# mcp23017-board.net
KiCad netlist of a schematic drawn in EAGLE
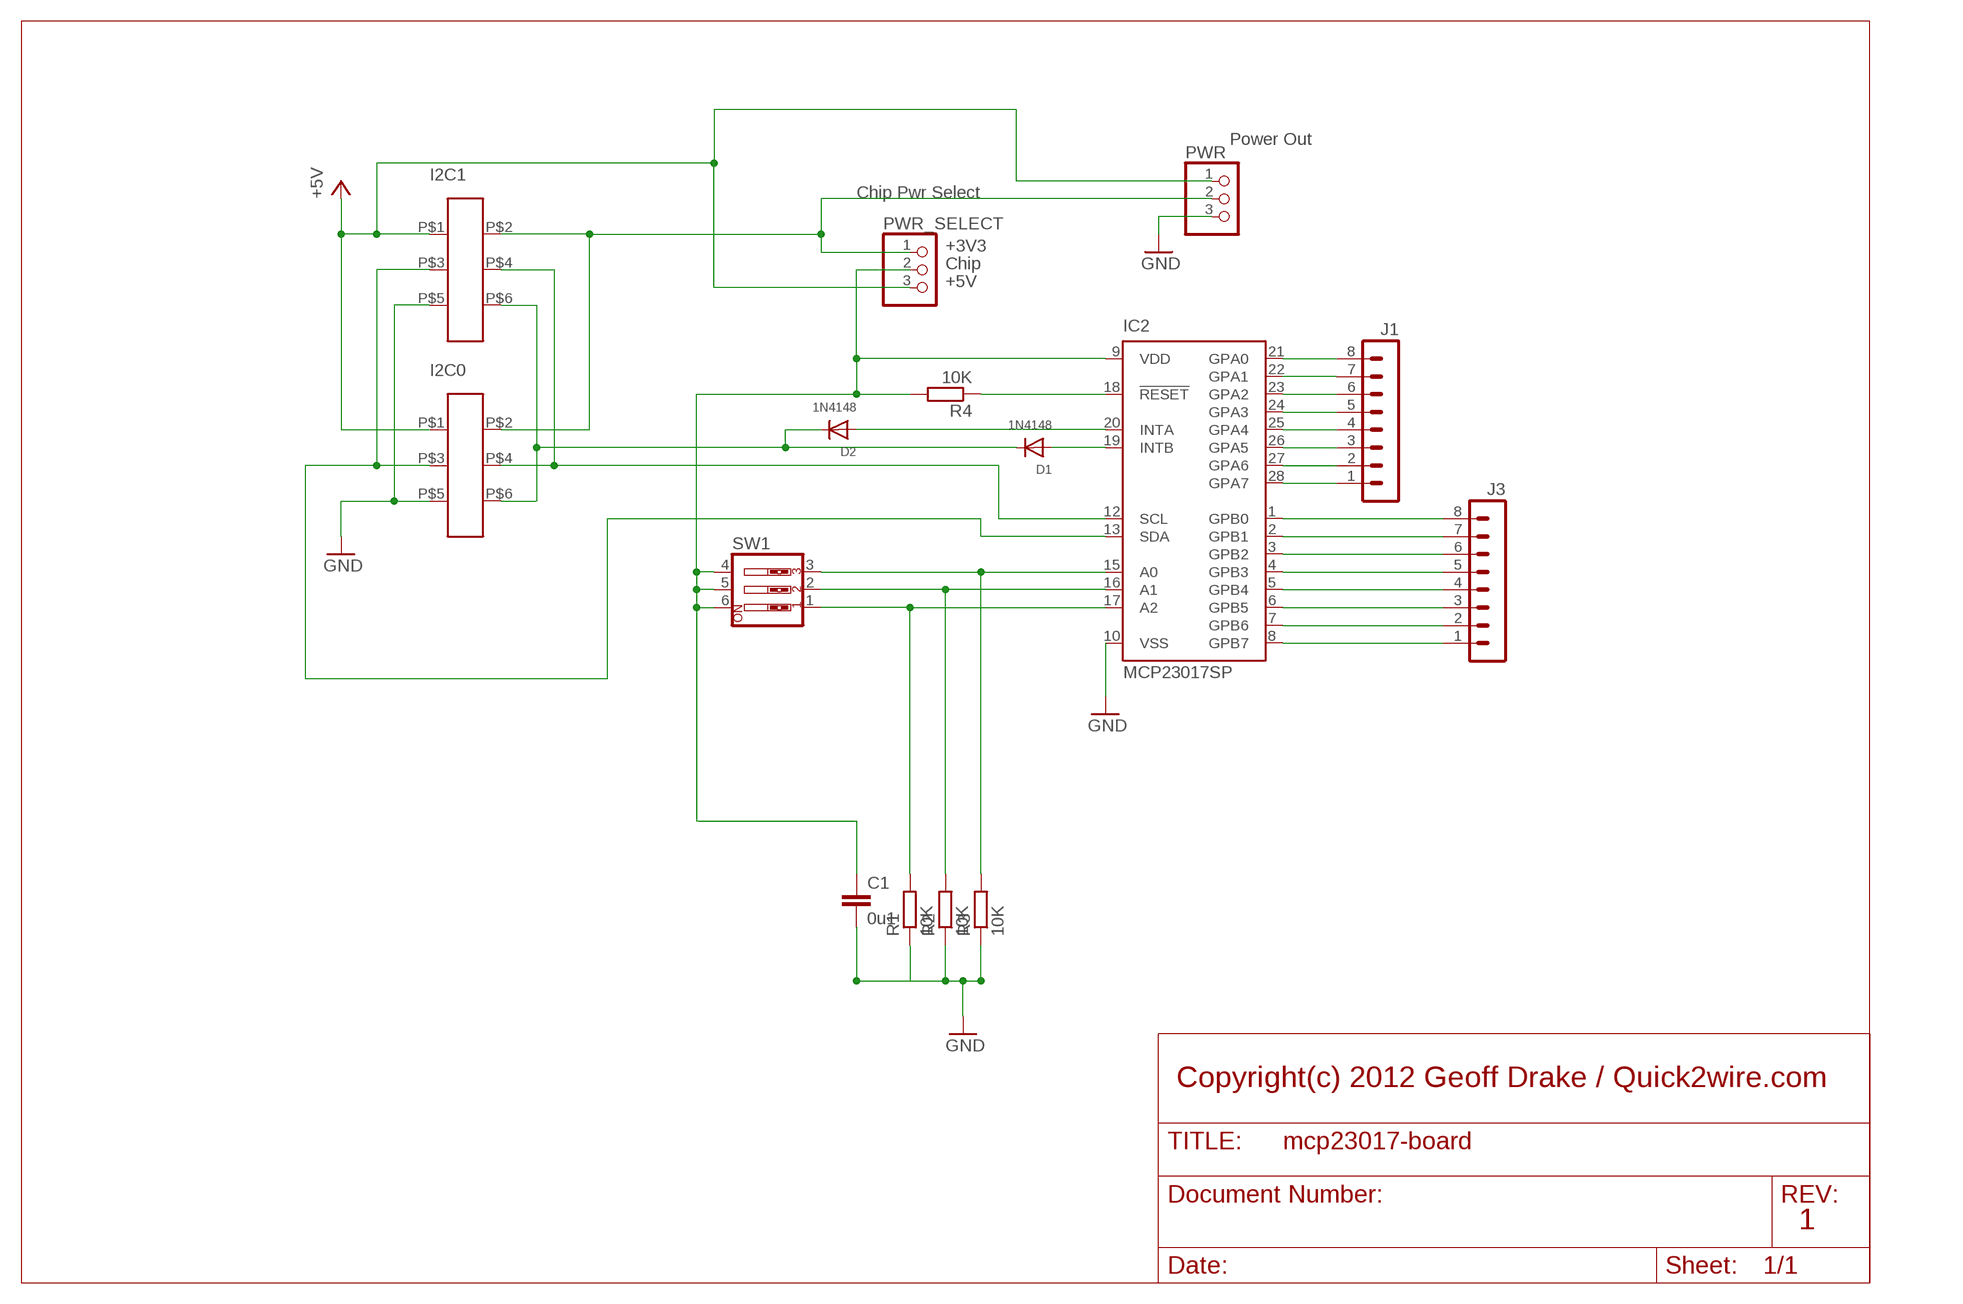
[diagram p0: schematic, sheet 1]

(export (version "E")
  (design (tool "Eeschema 10.0.6"))
  (components
    (comp (ref "C1")
      (value "0u1")
      (footprint "eagle-import:C025-030X050")
      (libsource (lib "eagle-import") (part "C-EU025-030X050"))
    )
    (comp (ref "D1")
      (value "1N4148")
      (footprint "eagle-import:DO-1N4148")
      (libsource (lib "eagle-import") (part "DIODEDO-1N4148"))
    )
    (comp (ref "D2")
      (value "1N4148")
      (footprint "eagle-import:DO-1N4148")
      (libsource (lib "eagle-import") (part "DIODEDO-1N4148"))
    )
    (comp (ref "I2C0")
      (value "IDC-6W")
      (footprint "eagle-import:IDC-6W")
      (libsource (lib "eagle-import") (part "IDC-6W"))
    )
    (comp (ref "I2C1")
      (value "IDC-6W")
      (footprint "eagle-import:IDC-6W")
      (libsource (lib "eagle-import") (part "IDC-6W"))
    )
    (comp (ref "IC2")
      (value "MCP23017SP")
      (footprint "eagle-import:DIL28-3")
      (libsource (lib "eagle-import") (part "MCP23017SP"))
    )
    (comp (ref "J1")
      (value "MA08-1")
      (footprint "eagle-import:MA08-1")
      (fields (field (name "OC_FARNELL") "unknown") (field (name "OC_NEWARK") "unknown"))
      (libsource (lib "eagle-import") (part "MA08-1"))
    )
    (comp (ref "J3")
      (value "MA08-1")
      (footprint "eagle-import:MA08-1")
      (libsource (lib "eagle-import") (part "MA08-1"))
    )
    (comp (ref "PWR")
      (value "PINHD-1X3")
      (footprint "eagle-import:1X03")
      (libsource (lib "eagle-import") (part "PINHD-1X3"))
    )
    (comp (ref "PWR_SELECT")
      (value "PINHD-1X3")
      (footprint "eagle-import:1X03")
      (libsource (lib "eagle-import") (part "PINHD-1X3"))
    )
    (comp (ref "R1")
      (value "10K")
      (footprint "eagle-import:0207_10")
      (libsource (lib "eagle-import") (part "R-EU_0207/10"))
    )
    (comp (ref "R2")
      (value "10K")
      (footprint "eagle-import:0207_10")
      (libsource (lib "eagle-import") (part "R-EU_0207/10"))
    )
    (comp (ref "R3")
      (value "10K")
      (footprint "eagle-import:0207_10")
      (libsource (lib "eagle-import") (part "R-EU_0207/10"))
    )
    (comp (ref "R4")
      (value "10K")
      (footprint "eagle-import:0207_10")
      (libsource (lib "eagle-import") (part "R-EU_0207/10"))
    )
    (comp (ref "SW1")
      (value "SW_DIP-3")
      (footprint "eagle-import:EDG-03")
      (libsource (lib "eagle-import") (part "SW_DIP-3"))
    )
  )
  (nets
    (net (code "1") (name "+5V") (class "Default")
      (node (ref "I2C0") (pin "P$1") (pinfunction "P$1_P$1") (pintype "bidirectional"))
      (node (ref "I2C1") (pin "P$1") (pinfunction "P$1_P$1") (pintype "bidirectional"))
      (node (ref "PWR") (pin "1") (pinfunction "1_1") (pintype "passive"))
      (node (ref "PWR_SELECT") (pin "3") (pinfunction "3_3") (pintype "passive"))
    )
    (net (code "2") (name "GND") (class "Default")
      (node (ref "C1") (pin "2") (pinfunction "2_2") (pintype "passive"))
      (node (ref "I2C0") (pin "P$5") (pinfunction "P$5_P$5") (pintype "bidirectional"))
      (node (ref "I2C1") (pin "P$5") (pinfunction "P$5_P$5") (pintype "bidirectional"))
      (node (ref "IC2") (pin "10") (pinfunction "VSS_10") (pintype "power_in"))
      (node (ref "PWR") (pin "3") (pinfunction "3_3") (pintype "passive"))
      (node (ref "R1") (pin "1") (pinfunction "1_1") (pintype "passive"))
      (node (ref "R2") (pin "1") (pinfunction "1_1") (pintype "passive"))
      (node (ref "R3") (pin "1") (pinfunction "1_1") (pintype "passive"))
    )
    (net (code "3") (name "Net-(D1-PadC)") (class "Default")
      (node (ref "D1") (pin "C") (pinfunction "C_C") (pintype "passive"))
      (node (ref "D2") (pin "C") (pinfunction "C_C") (pintype "passive"))
      (node (ref "I2C0") (pin "P$6") (pinfunction "P$6_P$6") (pintype "bidirectional"))
      (node (ref "I2C1") (pin "P$6") (pinfunction "P$6_P$6") (pintype "bidirectional"))
    )
    (net (code "4") (name "Net-(I2C0-PadP$2)") (class "Default")
      (node (ref "I2C0") (pin "P$2") (pinfunction "P$2_P$2") (pintype "bidirectional"))
      (node (ref "I2C1") (pin "P$2") (pinfunction "P$2_P$2") (pintype "bidirectional"))
      (node (ref "PWR") (pin "2") (pinfunction "2_2") (pintype "passive"))
      (node (ref "PWR_SELECT") (pin "1") (pinfunction "1_1") (pintype "passive"))
    )
    (net (code "5") (name "Net-(IC2-A0)") (class "Default")
      (node (ref "IC2") (pin "15") (pinfunction "A0_15") (pintype "input"))
      (node (ref "R3") (pin "2") (pinfunction "2_2") (pintype "passive"))
      (node (ref "SW1") (pin "3") (pinfunction "3_3") (pintype "passive"))
    )
    (net (code "6") (name "Net-(IC2-A1)") (class "Default")
      (node (ref "IC2") (pin "16") (pinfunction "A1_16") (pintype "input"))
      (node (ref "R2") (pin "2") (pinfunction "2_2") (pintype "passive"))
      (node (ref "SW1") (pin "2") (pinfunction "2_2") (pintype "passive"))
    )
    (net (code "7") (name "Net-(IC2-A2)") (class "Default")
      (node (ref "IC2") (pin "17") (pinfunction "A2_17") (pintype "input"))
      (node (ref "R1") (pin "2") (pinfunction "2_2") (pintype "passive"))
      (node (ref "SW1") (pin "1") (pinfunction "1_1") (pintype "passive"))
    )
    (net (code "8") (name "Net-(IC2-GPA0)") (class "Default")
      (node (ref "IC2") (pin "21") (pinfunction "GPA0_21") (pintype "bidirectional"))
      (node (ref "J1") (pin "8") (pinfunction "8_8") (pintype "passive"))
    )
    (net (code "9") (name "Net-(IC2-GPA1)") (class "Default")
      (node (ref "IC2") (pin "22") (pinfunction "GPA1_22") (pintype "bidirectional"))
      (node (ref "J1") (pin "7") (pinfunction "7_7") (pintype "passive"))
    )
    (net (code "10") (name "Net-(IC2-GPA2)") (class "Default")
      (node (ref "IC2") (pin "23") (pinfunction "GPA2_23") (pintype "bidirectional"))
      (node (ref "J1") (pin "6") (pinfunction "6_6") (pintype "passive"))
    )
    (net (code "11") (name "Net-(IC2-GPA3)") (class "Default")
      (node (ref "IC2") (pin "24") (pinfunction "GPA3_24") (pintype "bidirectional"))
      (node (ref "J1") (pin "5") (pinfunction "5_5") (pintype "passive"))
    )
    (net (code "12") (name "Net-(IC2-GPA4)") (class "Default")
      (node (ref "IC2") (pin "25") (pinfunction "GPA4_25") (pintype "bidirectional"))
      (node (ref "J1") (pin "4") (pinfunction "4_4") (pintype "passive"))
    )
    (net (code "13") (name "Net-(IC2-GPA5)") (class "Default")
      (node (ref "IC2") (pin "26") (pinfunction "GPA5_26") (pintype "bidirectional"))
      (node (ref "J1") (pin "3") (pinfunction "3_3") (pintype "passive"))
    )
    (net (code "14") (name "Net-(IC2-GPA6)") (class "Default")
      (node (ref "IC2") (pin "27") (pinfunction "GPA6_27") (pintype "bidirectional"))
      (node (ref "J1") (pin "2") (pinfunction "2_2") (pintype "passive"))
    )
    (net (code "15") (name "Net-(IC2-GPA7)") (class "Default")
      (node (ref "IC2") (pin "28") (pinfunction "GPA7_28") (pintype "bidirectional"))
      (node (ref "J1") (pin "1") (pinfunction "1_1") (pintype "passive"))
    )
    (net (code "16") (name "Net-(IC2-GPB0)") (class "Default")
      (node (ref "IC2") (pin "1") (pinfunction "GPB0_1") (pintype "bidirectional"))
      (node (ref "J3") (pin "8") (pinfunction "8_8") (pintype "passive"))
    )
    (net (code "17") (name "Net-(IC2-GPB1)") (class "Default")
      (node (ref "IC2") (pin "2") (pinfunction "GPB1_2") (pintype "bidirectional"))
      (node (ref "J3") (pin "7") (pinfunction "7_7") (pintype "passive"))
    )
    (net (code "18") (name "Net-(IC2-GPB2)") (class "Default")
      (node (ref "IC2") (pin "3") (pinfunction "GPB2_3") (pintype "bidirectional"))
      (node (ref "J3") (pin "6") (pinfunction "6_6") (pintype "passive"))
    )
    (net (code "19") (name "Net-(IC2-GPB3)") (class "Default")
      (node (ref "IC2") (pin "4") (pinfunction "GPB3_4") (pintype "bidirectional"))
      (node (ref "J3") (pin "5") (pinfunction "5_5") (pintype "passive"))
    )
    (net (code "20") (name "Net-(IC2-GPB4)") (class "Default")
      (node (ref "IC2") (pin "5") (pinfunction "GPB4_5") (pintype "bidirectional"))
      (node (ref "J3") (pin "4") (pinfunction "4_4") (pintype "passive"))
    )
    (net (code "21") (name "Net-(IC2-GPB5)") (class "Default")
      (node (ref "IC2") (pin "6") (pinfunction "GPB5_6") (pintype "bidirectional"))
      (node (ref "J3") (pin "3") (pinfunction "3_3") (pintype "passive"))
    )
    (net (code "22") (name "Net-(IC2-GPB6)") (class "Default")
      (node (ref "IC2") (pin "7") (pinfunction "GPB6_7") (pintype "bidirectional"))
      (node (ref "J3") (pin "2") (pinfunction "2_2") (pintype "passive"))
    )
    (net (code "23") (name "Net-(IC2-GPB7)") (class "Default")
      (node (ref "IC2") (pin "8") (pinfunction "GPB7_8") (pintype "bidirectional"))
      (node (ref "J3") (pin "1") (pinfunction "1_1") (pintype "passive"))
    )
    (net (code "24") (name "Net-(IC2-INTA)") (class "Default")
      (node (ref "D2") (pin "A") (pinfunction "A_A") (pintype "passive"))
      (node (ref "IC2") (pin "20") (pinfunction "INTA_20") (pintype "output"))
    )
    (net (code "25") (name "Net-(IC2-INTB)") (class "Default")
      (node (ref "D1") (pin "A") (pinfunction "A_A") (pintype "passive"))
      (node (ref "IC2") (pin "19") (pinfunction "INTB_19") (pintype "output"))
    )
    (net (code "26") (name "Net-(IC2-SCL)") (class "Default")
      (node (ref "I2C0") (pin "P$4") (pinfunction "P$4_P$4") (pintype "bidirectional"))
      (node (ref "I2C1") (pin "P$4") (pinfunction "P$4_P$4") (pintype "bidirectional"))
      (node (ref "IC2") (pin "12") (pinfunction "SCL_12") (pintype "input"))
    )
    (net (code "27") (name "Net-(IC2-SDA)") (class "Default")
      (node (ref "I2C0") (pin "P$3") (pinfunction "P$3_P$3") (pintype "bidirectional"))
      (node (ref "I2C1") (pin "P$3") (pinfunction "P$3_P$3") (pintype "bidirectional"))
      (node (ref "IC2") (pin "13") (pinfunction "SDA_13") (pintype "bidirectional"))
    )
    (net (code "28") (name "Net-(IC2-VDD)") (class "Default")
      (node (ref "C1") (pin "1") (pinfunction "1_1") (pintype "passive"))
      (node (ref "IC2") (pin "9") (pinfunction "VDD_9") (pintype "power_in"))
      (node (ref "PWR_SELECT") (pin "2") (pinfunction "2_2") (pintype "passive"))
      (node (ref "R4") (pin "2") (pinfunction "2_2") (pintype "passive"))
      (node (ref "SW1") (pin "4") (pinfunction "4_4") (pintype "passive"))
      (node (ref "SW1") (pin "5") (pinfunction "5_5") (pintype "passive"))
      (node (ref "SW1") (pin "6") (pinfunction "6_6") (pintype "passive"))
    )
    (net (code "29") (name "Net-(IC2-~{RESET})") (class "Default")
      (node (ref "IC2") (pin "18") (pinfunction "~{RESET}_18") (pintype "input"))
      (node (ref "R4") (pin "1") (pinfunction "1_1") (pintype "passive"))
    )
  )
)
